# robotrev2.net
KiCad netlist of a schematic drawn in EAGLE
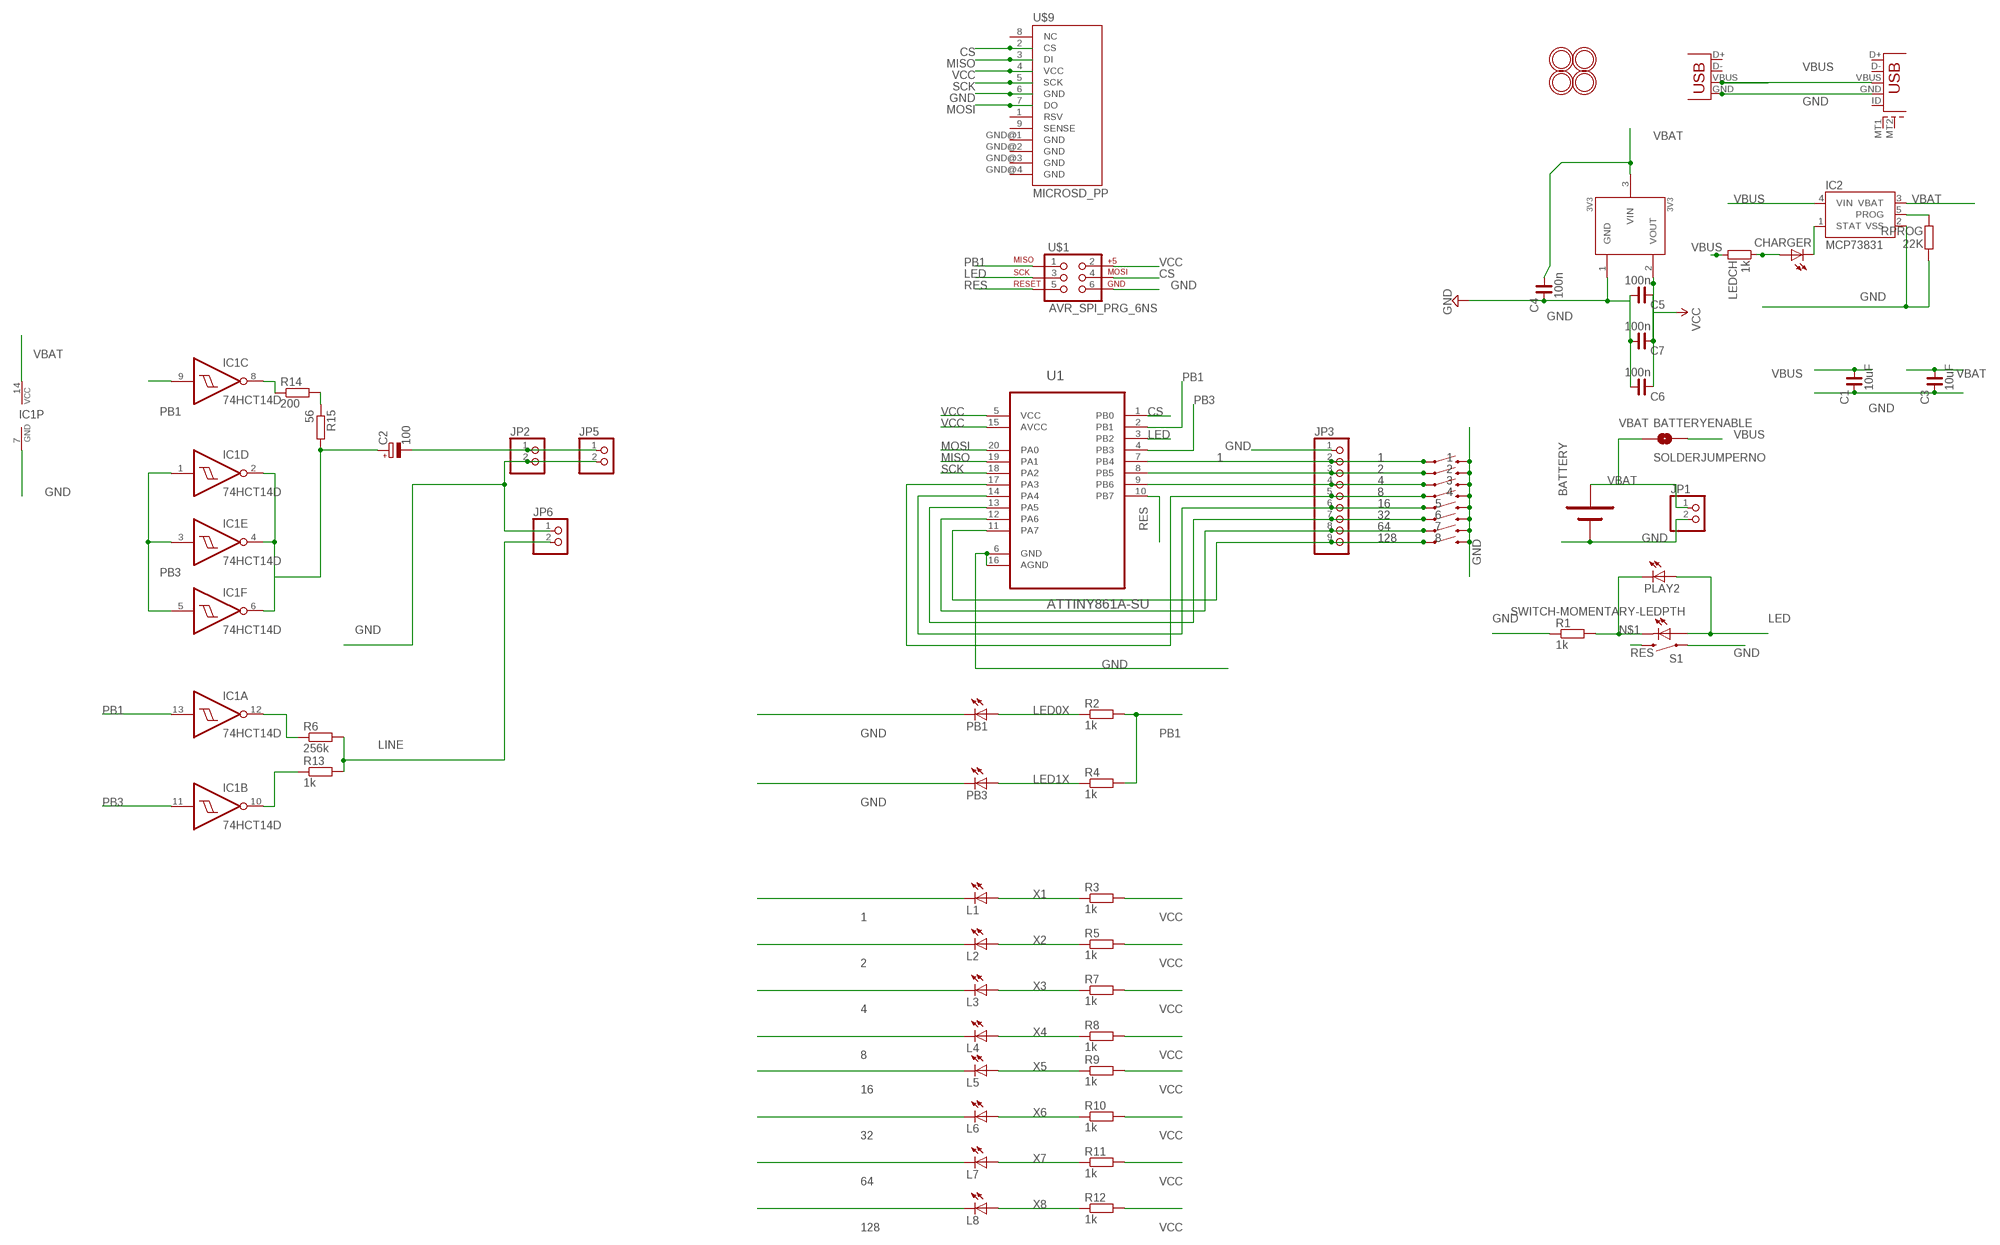
[diagram p0: schematic, sheet 1]

(export (version "E")
  (design (tool "Eeschema 10.0.6"))
  (components
    (comp (ref "1")
      (value "SWITCH-MOMENTARY-2-SMD-1101NE")
      (footprint "eagle-import:TACTILE-SWITCH-1101NE")
      (libsource (lib "eagle-import") (part "SWITCH-MOMENTARY-2-SMD-1101NE"))
    )
    (comp (ref "2")
      (value "SWITCH-MOMENTARY-2-SMD-1101NE")
      (footprint "eagle-import:TACTILE-SWITCH-1101NE")
      (libsource (lib "eagle-import") (part "SWITCH-MOMENTARY-2-SMD-1101NE"))
    )
    (comp (ref "3")
      (value "SWITCH-MOMENTARY-2-SMD-1101NE")
      (footprint "eagle-import:TACTILE-SWITCH-1101NE")
      (libsource (lib "eagle-import") (part "SWITCH-MOMENTARY-2-SMD-1101NE"))
    )
    (comp (ref "3V3")
      (value "3V3")
      (footprint "eagle-import:SOT23")
      (libsource (lib "eagle-import") (part "MCP1700T"))
    )
    (comp (ref "4")
      (value "SWITCH-MOMENTARY-2-SMD-1101NE")
      (footprint "eagle-import:TACTILE-SWITCH-1101NE")
      (libsource (lib "eagle-import") (part "SWITCH-MOMENTARY-2-SMD-1101NE"))
    )
    (comp (ref "5")
      (value "SWITCH-MOMENTARY-2-SMD-1101NE")
      (footprint "eagle-import:TACTILE-SWITCH-1101NE")
      (libsource (lib "eagle-import") (part "SWITCH-MOMENTARY-2-SMD-1101NE"))
    )
    (comp (ref "6")
      (value "SWITCH-MOMENTARY-2-SMD-1101NE")
      (footprint "eagle-import:TACTILE-SWITCH-1101NE")
      (libsource (lib "eagle-import") (part "SWITCH-MOMENTARY-2-SMD-1101NE"))
    )
    (comp (ref "7")
      (value "SWITCH-MOMENTARY-2-SMD-1101NE")
      (footprint "eagle-import:TACTILE-SWITCH-1101NE")
      (libsource (lib "eagle-import") (part "SWITCH-MOMENTARY-2-SMD-1101NE"))
    )
    (comp (ref "8")
      (value "SWITCH-MOMENTARY-2-SMD-1101NE")
      (footprint "eagle-import:TACTILE-SWITCH-1101NE")
      (libsource (lib "eagle-import") (part "SWITCH-MOMENTARY-2-SMD-1101NE"))
    )
    (comp (ref "BATTERY")
      (value "BATTERY-1XAA20MM")
      (footprint "eagle-import:BATTCOM_20MM_PTH")
      (libsource (lib "eagle-import") (part "BATTERY-1XAA20MM"))
    )
    (comp (ref "BATTERYENABLE")
      (value "SOLDERJUMPERNO")
      (footprint "eagle-import:SJ_2S-NO")
      (libsource (lib "eagle-import") (part "SOLDERJUMPERNO"))
    )
    (comp (ref "C1")
      (value "10uF")
      (footprint "eagle-import:C0603")
      (libsource (lib "eagle-import") (part "C_0603"))
    )
    (comp (ref "C2")
      (value "100")
      (footprint "eagle-import:153CLV-0605")
      (libsource (lib "eagle-import") (part "CPOL-EU153CLV-0605"))
    )
    (comp (ref "C3")
      (value "10uF")
      (footprint "eagle-import:C0603")
      (libsource (lib "eagle-import") (part "C_0603"))
    )
    (comp (ref "C4")
      (value "100n")
      (footprint "eagle-import:C0603")
      (libsource (lib "eagle-import") (part "C_0603"))
    )
    (comp (ref "C5")
      (value "100n")
      (footprint "eagle-import:C0603")
      (libsource (lib "eagle-import") (part "C_0603"))
    )
    (comp (ref "C6")
      (value "100n")
      (footprint "eagle-import:C0603")
      (libsource (lib "eagle-import") (part "C_0603"))
    )
    (comp (ref "C7")
      (value "100n")
      (footprint "eagle-import:C0603")
      (libsource (lib "eagle-import") (part "C_0603"))
    )
    (comp (ref "CHARGER")
      (value "LEDSML0603")
      (footprint "eagle-import:SML0603")
      (libsource (lib "eagle-import") (part "LEDSML0603"))
    )
    (comp (ref "IC1")
      (value "74HCT14D")
      (footprint "eagle-import:SO14")
      (libsource (lib "eagle-import") (part "7414DHCT"))
    )
    (comp (ref "IC2")
      (value "MCP73831")
      (footprint "eagle-import:SOT23-5")
      (libsource (lib "eagle-import") (part "MCP73831"))
    )
    (comp (ref "JP1")
      (value "PINHD-1X2")
      (footprint "eagle-import:1X02")
      (libsource (lib "eagle-import") (part "PINHD-1X2"))
    )
    (comp (ref "JP2")
      (value "PINHD-1X2")
      (footprint "eagle-import:1X02")
      (libsource (lib "eagle-import") (part "PINHD-1X2"))
    )
    (comp (ref "JP3")
      (value "PINHD-1X9")
      (footprint "eagle-import:1X09")
      (libsource (lib "eagle-import") (part "PINHD-1X9"))
    )
    (comp (ref "JP5")
      (value "PINHD-1X2")
      (footprint "eagle-import:1X02")
      (libsource (lib "eagle-import") (part "PINHD-1X2"))
    )
    (comp (ref "JP6")
      (value "PINHD-1X2")
      (footprint "eagle-import:1X02")
      (libsource (lib "eagle-import") (part "PINHD-1X2"))
    )
    (comp (ref "L1")
      (value "LEDSML0603")
      (footprint "eagle-import:SML0603")
      (libsource (lib "eagle-import") (part "LEDSML0603"))
    )
    (comp (ref "L2")
      (value "LEDSML0603")
      (footprint "eagle-import:SML0603")
      (libsource (lib "eagle-import") (part "LEDSML0603"))
    )
    (comp (ref "L3")
      (value "LEDSML0603")
      (footprint "eagle-import:SML0603")
      (libsource (lib "eagle-import") (part "LEDSML0603"))
    )
    (comp (ref "L4")
      (value "LEDSML0603")
      (footprint "eagle-import:SML0603")
      (libsource (lib "eagle-import") (part "LEDSML0603"))
    )
    (comp (ref "L5")
      (value "LEDSML0603")
      (footprint "eagle-import:SML0603")
      (libsource (lib "eagle-import") (part "LEDSML0603"))
    )
    (comp (ref "L6")
      (value "LEDSML0603")
      (footprint "eagle-import:SML0603")
      (libsource (lib "eagle-import") (part "LEDSML0603"))
    )
    (comp (ref "L7")
      (value "LEDSML0603")
      (footprint "eagle-import:SML0603")
      (libsource (lib "eagle-import") (part "LEDSML0603"))
    )
    (comp (ref "L8")
      (value "LEDSML0603")
      (footprint "eagle-import:SML0603")
      (libsource (lib "eagle-import") (part "LEDSML0603"))
    )
    (comp (ref "LEDCH")
      (value "1k")
      (footprint "eagle-import:R0603")
      (libsource (lib "eagle-import") (part "R-EU_R0603"))
    )
    (comp (ref "PB1")
      (value "LEDSML0603")
      (footprint "eagle-import:SML0603")
      (libsource (lib "eagle-import") (part "LEDSML0603"))
    )
    (comp (ref "PB3")
      (value "LEDSML0603")
      (footprint "eagle-import:SML0603")
      (libsource (lib "eagle-import") (part "LEDSML0603"))
    )
    (comp (ref "PLAY2")
      (value "LEDSML0603")
      (footprint "eagle-import:SML0603")
      (libsource (lib "eagle-import") (part "LEDSML0603"))
    )
    (comp (ref "R1")
      (value "1k")
      (footprint "eagle-import:R0603")
      (libsource (lib "eagle-import") (part "resistor_R-EU_R0603"))
    )
    (comp (ref "R2")
      (value "1k")
      (footprint "eagle-import:R0603")
      (libsource (lib "eagle-import") (part "resistor_R-EU_R0603"))
    )
    (comp (ref "R3")
      (value "1k")
      (footprint "eagle-import:R0603")
      (libsource (lib "eagle-import") (part "resistor_R-EU_R0603"))
    )
    (comp (ref "R4")
      (value "1k")
      (footprint "eagle-import:R0603")
      (libsource (lib "eagle-import") (part "resistor_R-EU_R0603"))
    )
    (comp (ref "R5")
      (value "1k")
      (footprint "eagle-import:R0603")
      (libsource (lib "eagle-import") (part "resistor_R-EU_R0603"))
    )
    (comp (ref "R6")
      (value "256k")
      (footprint "eagle-import:R0603")
      (libsource (lib "eagle-import") (part "resistor_R-EU_R0603"))
    )
    (comp (ref "R7")
      (value "1k")
      (footprint "eagle-import:R0603")
      (libsource (lib "eagle-import") (part "resistor_R-EU_R0603"))
    )
    (comp (ref "R8")
      (value "1k")
      (footprint "eagle-import:R0603")
      (libsource (lib "eagle-import") (part "resistor_R-EU_R0603"))
    )
    (comp (ref "R9")
      (value "1k")
      (footprint "eagle-import:R0603")
      (libsource (lib "eagle-import") (part "resistor_R-EU_R0603"))
    )
    (comp (ref "R10")
      (value "1k")
      (footprint "eagle-import:R0603")
      (libsource (lib "eagle-import") (part "resistor_R-EU_R0603"))
    )
    (comp (ref "R11")
      (value "1k")
      (footprint "eagle-import:R0603")
      (libsource (lib "eagle-import") (part "resistor_R-EU_R0603"))
    )
    (comp (ref "R12")
      (value "1k")
      (footprint "eagle-import:R0603")
      (libsource (lib "eagle-import") (part "resistor_R-EU_R0603"))
    )
    (comp (ref "R13")
      (value "1k")
      (footprint "eagle-import:R0603")
      (libsource (lib "eagle-import") (part "resistor_R-EU_R0603"))
    )
    (comp (ref "R14")
      (value "200")
      (footprint "eagle-import:R0603")
      (libsource (lib "eagle-import") (part "resistor_R-EU_R0603"))
    )
    (comp (ref "R15")
      (value "56")
      (footprint "eagle-import:R0603")
      (libsource (lib "eagle-import") (part "resistor_R-EU_R0603"))
    )
    (comp (ref "RPROG")
      (value "22K")
      (footprint "eagle-import:R0603")
      (libsource (lib "eagle-import") (part "R-EU_R0603"))
    )
    (comp (ref "S1")
      (value "SWITCH-MOMENTARY-LEDPTH")
      (footprint "eagle-import:TACTILE-PTH-LED-12MM")
      (libsource (lib "eagle-import") (part "SWITCH-MOMENTARY-LEDPTH"))
    )
    (comp (ref "U$1")
      (value "AVR_SPI_PRG_6NS")
      (footprint "eagle-import:2X3-NS")
      (libsource (lib "eagle-import") (part "AVR_SPI_PRG_6NS"))
    )
    (comp (ref "U$3")
      (value "MOUNTINGHOLE2.0")
      (footprint "eagle-import:MOUNTINGHOLE_2.0_PLATED")
      (libsource (lib "eagle-import") (part "MOUNTINGHOLE2.0"))
    )
    (comp (ref "U$4")
      (value "MOUNTINGHOLE2.0")
      (footprint "eagle-import:MOUNTINGHOLE_2.0_PLATED")
      (libsource (lib "eagle-import") (part "MOUNTINGHOLE2.0"))
    )
    (comp (ref "U$6")
      (value "MOUNTINGHOLE2.0")
      (footprint "eagle-import:MOUNTINGHOLE_2.0_PLATED")
      (libsource (lib "eagle-import") (part "MOUNTINGHOLE2.0"))
    )
    (comp (ref "U$7")
      (value "MOUNTINGHOLE2.0")
      (footprint "eagle-import:MOUNTINGHOLE_2.0_PLATED")
      (libsource (lib "eagle-import") (part "MOUNTINGHOLE2.0"))
    )
    (comp (ref "U$9")
      (value "MICROSD_PP")
      (footprint "eagle-import:MICROSD_PP")
      (libsource (lib "eagle-import") (part "MICROSD_PP"))
    )
    (comp (ref "U1")
      (value "ATTINY861A-SU")
      (footprint "eagle-import:SOIC127P1032X265-20N")
      (libsource (lib "eagle-import") (part "ATTINY861A-SU"))
    )
    (comp (ref "USB1")
      (value "USB-MICROBLARGEPAD")
      (footprint "eagle-import:USB-MICROB_LARGEPAD")
      (libsource (lib "eagle-import") (part "USB-MICROBLARGEPAD"))
    )
    (comp (ref "X5")
      (value "USBSMD")
      (footprint "eagle-import:USB-MINIB")
      (libsource (lib "eagle-import") (part "USBSMD"))
    )
  )
  (nets
    (net (code "1") (name "/1") (class "Default")
      (node (ref "1") (pin "P$1") (pinfunction "1_P$1") (pintype "passive"))
      (node (ref "JP3") (pin "2") (pinfunction "2_2") (pintype "passive"))
      (node (ref "L1") (pin "C") (pinfunction "C_C") (pintype "passive"))
      (node (ref "U1") (pin "7") (pinfunction "PB4_7") (pintype "bidirectional"))
    )
    (net (code "2") (name "/2") (class "Default")
      (node (ref "2") (pin "P$1") (pinfunction "1_P$1") (pintype "passive"))
      (node (ref "JP3") (pin "3") (pinfunction "3_3") (pintype "passive"))
      (node (ref "L2") (pin "C") (pinfunction "C_C") (pintype "passive"))
      (node (ref "U1") (pin "8") (pinfunction "PB5_8") (pintype "bidirectional"))
    )
    (net (code "3") (name "/4") (class "Default")
      (node (ref "3") (pin "P$1") (pinfunction "1_P$1") (pintype "passive"))
      (node (ref "JP3") (pin "4") (pinfunction "4_4") (pintype "passive"))
      (node (ref "L3") (pin "C") (pinfunction "C_C") (pintype "passive"))
      (node (ref "U1") (pin "9") (pinfunction "PB6_9") (pintype "bidirectional"))
    )
    (net (code "4") (name "/8") (class "Default")
      (node (ref "4") (pin "P$1") (pinfunction "1_P$1") (pintype "passive"))
      (node (ref "JP3") (pin "5") (pinfunction "5_5") (pintype "passive"))
      (node (ref "L4") (pin "C") (pinfunction "C_C") (pintype "passive"))
      (node (ref "U1") (pin "17") (pinfunction "PA3_17") (pintype "bidirectional"))
    )
    (net (code "5") (name "/16") (class "Default")
      (node (ref "5") (pin "P$1") (pinfunction "1_P$1") (pintype "passive"))
      (node (ref "JP3") (pin "6") (pinfunction "6_6") (pintype "passive"))
      (node (ref "L5") (pin "C") (pinfunction "C_C") (pintype "passive"))
      (node (ref "U1") (pin "14") (pinfunction "PA4_14") (pintype "bidirectional"))
    )
    (net (code "6") (name "/32") (class "Default")
      (node (ref "6") (pin "P$1") (pinfunction "1_P$1") (pintype "passive"))
      (node (ref "JP3") (pin "7") (pinfunction "7_7") (pintype "passive"))
      (node (ref "L6") (pin "C") (pinfunction "C_C") (pintype "passive"))
      (node (ref "U1") (pin "13") (pinfunction "PA5_13") (pintype "bidirectional"))
    )
    (net (code "7") (name "/64") (class "Default")
      (node (ref "7") (pin "P$1") (pinfunction "1_P$1") (pintype "passive"))
      (node (ref "JP3") (pin "8") (pinfunction "8_8") (pintype "passive"))
      (node (ref "L7") (pin "C") (pinfunction "C_C") (pintype "passive"))
      (node (ref "U1") (pin "12") (pinfunction "PA6_12") (pintype "bidirectional"))
    )
    (net (code "8") (name "/128") (class "Default")
      (node (ref "8") (pin "P$1") (pinfunction "1_P$1") (pintype "passive"))
      (node (ref "JP3") (pin "9") (pinfunction "9_9") (pintype "passive"))
      (node (ref "L8") (pin "C") (pinfunction "C_C") (pintype "passive"))
      (node (ref "U1") (pin "11") (pinfunction "PA7_11") (pintype "bidirectional"))
    )
    (net (code "9") (name "/CS") (class "Default")
      (node (ref "U$1") (pin "4") (pinfunction "4_4") (pintype "passive"))
      (node (ref "U$9") (pin "2") (pinfunction "CS_2") (pintype "bidirectional"))
      (node (ref "U1") (pin "1") (pinfunction "PB0_1") (pintype "bidirectional"))
    )
    (net (code "10") (name "/LED") (class "Default")
      (node (ref "PLAY2") (pin "A") (pinfunction "A_A") (pintype "passive"))
      (node (ref "S1") (pin "A") (pinfunction "A_A") (pintype "passive"))
      (node (ref "U$1") (pin "3") (pinfunction "3_3") (pintype "passive"))
      (node (ref "U1") (pin "3") (pinfunction "PB2_3") (pintype "bidirectional"))
    )
    (net (code "11") (name "/LED0X") (class "Default")
      (node (ref "PB1") (pin "A") (pinfunction "A_A") (pintype "passive"))
      (node (ref "R2") (pin "1") (pinfunction "1_1") (pintype "passive"))
    )
    (net (code "12") (name "/LED1X") (class "Default")
      (node (ref "PB3") (pin "A") (pinfunction "A_A") (pintype "passive"))
      (node (ref "R4") (pin "1") (pinfunction "1_1") (pintype "passive"))
    )
    (net (code "13") (name "/LINE") (class "Default")
      (node (ref "JP6") (pin "2") (pinfunction "2_2") (pintype "passive"))
      (node (ref "R13") (pin "2") (pinfunction "2_2") (pintype "passive"))
      (node (ref "R6") (pin "2") (pinfunction "2_2") (pintype "passive"))
    )
    (net (code "14") (name "/MISO") (class "Default")
      (node (ref "U$9") (pin "3") (pinfunction "DI_3") (pintype "bidirectional"))
      (node (ref "U1") (pin "19") (pinfunction "PA1_19") (pintype "bidirectional"))
    )
    (net (code "15") (name "/MOSI") (class "Default")
      (node (ref "U$9") (pin "7") (pinfunction "DO_7") (pintype "bidirectional"))
      (node (ref "U1") (pin "20") (pinfunction "PA0_20") (pintype "bidirectional"))
    )
    (net (code "16") (name "/N$1") (class "Default")
      (node (ref "PLAY2") (pin "C") (pinfunction "C_C") (pintype "passive"))
      (node (ref "R1") (pin "2") (pinfunction "2_2") (pintype "passive"))
      (node (ref "S1") (pin "C") (pinfunction "C_C") (pintype "passive"))
    )
    (net (code "17") (name "/PB1") (class "Default")
      (node (ref "IC1") (pin "13") (pinfunction "I_13") (pintype "input"))
      (node (ref "IC1") (pin "9") (pinfunction "I_9") (pintype "input"))
      (node (ref "R2") (pin "2") (pinfunction "2_2") (pintype "passive"))
      (node (ref "R4") (pin "2") (pinfunction "2_2") (pintype "passive"))
      (node (ref "U$1") (pin "1") (pinfunction "1_1") (pintype "passive"))
      (node (ref "U1") (pin "2") (pinfunction "PB1_2") (pintype "bidirectional"))
    )
    (net (code "18") (name "/PB3") (class "Default")
      (node (ref "IC1") (pin "1") (pinfunction "I_1") (pintype "input"))
      (node (ref "IC1") (pin "11") (pinfunction "I_11") (pintype "input"))
      (node (ref "IC1") (pin "3") (pinfunction "I_3") (pintype "input"))
      (node (ref "IC1") (pin "5") (pinfunction "I_5") (pintype "input"))
      (node (ref "U1") (pin "4") (pinfunction "PB3_4") (pintype "bidirectional"))
    )
    (net (code "19") (name "/RES") (class "Default")
      (node (ref "S1") (pin "2") (pinfunction "2_2") (pintype "passive"))
      (node (ref "U$1") (pin "5") (pinfunction "5_5") (pintype "passive"))
      (node (ref "U1") (pin "10") (pinfunction "PB7_10") (pintype "bidirectional"))
    )
    (net (code "20") (name "/SCK") (class "Default")
      (node (ref "U$9") (pin "5") (pinfunction "SCK_5") (pintype "bidirectional"))
      (node (ref "U1") (pin "18") (pinfunction "PA2_18") (pintype "bidirectional"))
    )
    (net (code "21") (name "/VBAT") (class "Default")
      (node (ref "3V3") (pin "3") (pinfunction "VIN_3") (pintype "bidirectional"))
      (node (ref "BATTERY") (pin "+") (pinfunction "+_+") (pintype "bidirectional"))
      (node (ref "BATTERYENABLE") (pin "1") (pinfunction "1_1") (pintype "passive"))
      (node (ref "C3") (pin "1") (pinfunction "1_1") (pintype "passive"))
      (node (ref "C4") (pin "1") (pinfunction "1_1") (pintype "passive"))
      (node (ref "IC1") (pin "14") (pinfunction "VCC_14") (pintype "power_in"))
      (node (ref "IC2") (pin "3") (pinfunction "VBAT_3") (pintype "power_in"))
      (node (ref "JP1") (pin "1") (pinfunction "1_1") (pintype "passive"))
    )
    (net (code "22") (name "/VBUS") (class "Default")
      (node (ref "BATTERYENABLE") (pin "2") (pinfunction "2_2") (pintype "passive"))
      (node (ref "C1") (pin "1") (pinfunction "1_1") (pintype "passive"))
      (node (ref "IC2") (pin "4") (pinfunction "VIN_4") (pintype "power_in"))
      (node (ref "LEDCH") (pin "2") (pinfunction "2_2") (pintype "passive"))
      (node (ref "USB1") (pin "VBUS") (pinfunction "VBUS_VBUS") (pintype "bidirectional"))
      (node (ref "X5") (pin "VBUS") (pinfunction "VBUS_VBUS") (pintype "bidirectional"))
    )
    (net (code "23") (name "/X1") (class "Default")
      (node (ref "L1") (pin "A") (pinfunction "A_A") (pintype "passive"))
      (node (ref "R3") (pin "1") (pinfunction "1_1") (pintype "passive"))
    )
    (net (code "24") (name "/X2") (class "Default")
      (node (ref "L2") (pin "A") (pinfunction "A_A") (pintype "passive"))
      (node (ref "R5") (pin "1") (pinfunction "1_1") (pintype "passive"))
    )
    (net (code "25") (name "/X3") (class "Default")
      (node (ref "L3") (pin "A") (pinfunction "A_A") (pintype "passive"))
      (node (ref "R7") (pin "1") (pinfunction "1_1") (pintype "passive"))
    )
    (net (code "26") (name "/X4") (class "Default")
      (node (ref "L4") (pin "A") (pinfunction "A_A") (pintype "passive"))
      (node (ref "R8") (pin "1") (pinfunction "1_1") (pintype "passive"))
    )
    (net (code "27") (name "/X5") (class "Default")
      (node (ref "L5") (pin "A") (pinfunction "A_A") (pintype "passive"))
      (node (ref "R9") (pin "1") (pinfunction "1_1") (pintype "passive"))
    )
    (net (code "28") (name "/X6") (class "Default")
      (node (ref "L6") (pin "A") (pinfunction "A_A") (pintype "passive"))
      (node (ref "R10") (pin "1") (pinfunction "1_1") (pintype "passive"))
    )
    (net (code "29") (name "/X7") (class "Default")
      (node (ref "L7") (pin "A") (pinfunction "A_A") (pintype "passive"))
      (node (ref "R11") (pin "1") (pinfunction "1_1") (pintype "passive"))
    )
    (net (code "30") (name "/X8") (class "Default")
      (node (ref "L8") (pin "A") (pinfunction "A_A") (pintype "passive"))
      (node (ref "R12") (pin "1") (pinfunction "1_1") (pintype "passive"))
    )
    (net (code "31") (name "GND") (class "Default")
      (node (ref "1") (pin "P$2") (pinfunction "2_P$2") (pintype "passive"))
      (node (ref "2") (pin "P$2") (pinfunction "2_P$2") (pintype "passive"))
      (node (ref "3") (pin "P$2") (pinfunction "2_P$2") (pintype "passive"))
      (node (ref "3V3") (pin "1") (pinfunction "GND_1") (pintype "bidirectional"))
      (node (ref "4") (pin "P$2") (pinfunction "2_P$2") (pintype "passive"))
      (node (ref "5") (pin "P$2") (pinfunction "2_P$2") (pintype "passive"))
      (node (ref "6") (pin "P$2") (pinfunction "2_P$2") (pintype "passive"))
      (node (ref "7") (pin "P$2") (pinfunction "2_P$2") (pintype "passive"))
      (node (ref "8") (pin "P$2") (pinfunction "2_P$2") (pintype "passive"))
      (node (ref "BATTERY") (pin "-") (pinfunction "-_-") (pintype "bidirectional"))
      (node (ref "C1") (pin "2") (pinfunction "2_2") (pintype "passive"))
      (node (ref "C3") (pin "2") (pinfunction "2_2") (pintype "passive"))
      (node (ref "C4") (pin "2") (pinfunction "2_2") (pintype "passive"))
      (node (ref "C5") (pin "1") (pinfunction "1_1") (pintype "passive"))
      (node (ref "C6") (pin "1") (pinfunction "1_1") (pintype "passive"))
      (node (ref "C7") (pin "1") (pinfunction "1_1") (pintype "passive"))
      (node (ref "IC1") (pin "7") (pinfunction "GND_7") (pintype "power_in"))
      (node (ref "IC2") (pin "2") (pinfunction "VSS_2") (pintype "power_in"))
      (node (ref "JP1") (pin "2") (pinfunction "2_2") (pintype "passive"))
      (node (ref "JP2") (pin "2") (pinfunction "2_2") (pintype "passive"))
      (node (ref "JP3") (pin "1") (pinfunction "1_1") (pintype "passive"))
      (node (ref "JP5") (pin "2") (pinfunction "2_2") (pintype "passive"))
      (node (ref "JP6") (pin "1") (pinfunction "1_1") (pintype "passive"))
      (node (ref "PB1") (pin "C") (pinfunction "C_C") (pintype "passive"))
      (node (ref "PB3") (pin "C") (pinfunction "C_C") (pintype "passive"))
      (node (ref "R1") (pin "1") (pinfunction "1_1") (pintype "passive"))
      (node (ref "RPROG") (pin "1") (pinfunction "1_1") (pintype "passive"))
      (node (ref "S1") (pin "4") (pinfunction "1_4") (pintype "passive"))
      (node (ref "U$1") (pin "6") (pinfunction "6_6") (pintype "passive"))
      (node (ref "U$9") (pin "6") (pinfunction "GND_6") (pintype "bidirectional"))
      (node (ref "U1") (pin "16") (pinfunction "AGND_16") (pintype "passive"))
      (node (ref "U1") (pin "6") (pinfunction "GND_6") (pintype "passive"))
      (node (ref "USB1") (pin "GND") (pinfunction "GND_GND") (pintype "bidirectional"))
      (node (ref "X5") (pin "GND") (pinfunction "GND_GND") (pintype "bidirectional"))
    )
    (net (code "32") (name "Net-(C2-Pad-)") (class "Default")
      (node (ref "C2") (pin "-") (pinfunction "-_-") (pintype "passive"))
      (node (ref "JP2") (pin "1") (pinfunction "1_1") (pintype "passive"))
      (node (ref "JP5") (pin "1") (pinfunction "1_1") (pintype "passive"))
    )
    (net (code "33") (name "Net-(CHARGER-PadA)") (class "Default")
      (node (ref "CHARGER") (pin "A") (pinfunction "A_A") (pintype "passive"))
      (node (ref "LEDCH") (pin "1") (pinfunction "1_1") (pintype "passive"))
    )
    (net (code "34") (name "Net-(IC1A-O)") (class "Default")
      (node (ref "IC1") (pin "12") (pinfunction "O_12") (pintype "output"))
      (node (ref "R6") (pin "1") (pinfunction "1_1") (pintype "passive"))
    )
    (net (code "35") (name "Net-(IC1B-O)") (class "Default")
      (node (ref "IC1") (pin "10") (pinfunction "O_10") (pintype "output"))
      (node (ref "R13") (pin "1") (pinfunction "1_1") (pintype "passive"))
    )
    (net (code "36") (name "Net-(IC1C-O)") (class "Default")
      (node (ref "IC1") (pin "8") (pinfunction "O_8") (pintype "output"))
      (node (ref "R14") (pin "1") (pinfunction "1_1") (pintype "passive"))
    )
    (net (code "37") (name "Net-(IC1D-O)") (class "Default")
      (node (ref "C2") (pin "+") (pinfunction "+_+") (pintype "passive"))
      (node (ref "IC1") (pin "2") (pinfunction "O_2") (pintype "output"))
      (node (ref "IC1") (pin "4") (pinfunction "O_4") (pintype "output"))
      (node (ref "IC1") (pin "6") (pinfunction "O_6") (pintype "output"))
      (node (ref "R15") (pin "2") (pinfunction "2_2") (pintype "passive"))
    )
    (net (code "38") (name "Net-(IC2-PROG)") (class "Default")
      (node (ref "IC2") (pin "5") (pinfunction "PROG_5") (pintype "input"))
      (node (ref "RPROG") (pin "2") (pinfunction "2_2") (pintype "passive"))
    )
    (net (code "39") (name "Net-(IC2-STAT)") (class "Default")
      (node (ref "CHARGER") (pin "C") (pinfunction "C_C") (pintype "passive"))
      (node (ref "IC2") (pin "1") (pinfunction "STAT_1") (pintype "output"))
    )
    (net (code "40") (name "Net-(R14-Pad2)") (class "Default")
      (node (ref "R14") (pin "2") (pinfunction "2_2") (pintype "passive"))
      (node (ref "R15") (pin "1") (pinfunction "1_1") (pintype "passive"))
    )
    (net (code "41") (name "VCC") (class "Default")
      (node (ref "3V3") (pin "2") (pinfunction "VOUT_2") (pintype "bidirectional"))
      (node (ref "C5") (pin "2") (pinfunction "2_2") (pintype "passive"))
      (node (ref "C6") (pin "2") (pinfunction "2_2") (pintype "passive"))
      (node (ref "C7") (pin "2") (pinfunction "2_2") (pintype "passive"))
      (node (ref "R10") (pin "2") (pinfunction "2_2") (pintype "passive"))
      (node (ref "R11") (pin "2") (pinfunction "2_2") (pintype "passive"))
      (node (ref "R12") (pin "2") (pinfunction "2_2") (pintype "passive"))
      (node (ref "R3") (pin "2") (pinfunction "2_2") (pintype "passive"))
      (node (ref "R5") (pin "2") (pinfunction "2_2") (pintype "passive"))
      (node (ref "R7") (pin "2") (pinfunction "2_2") (pintype "passive"))
      (node (ref "R8") (pin "2") (pinfunction "2_2") (pintype "passive"))
      (node (ref "R9") (pin "2") (pinfunction "2_2") (pintype "passive"))
      (node (ref "U$1") (pin "2") (pinfunction "2_2") (pintype "passive"))
      (node (ref "U$9") (pin "4") (pinfunction "VCC_4") (pintype "bidirectional"))
      (node (ref "U1") (pin "15") (pinfunction "AVCC_15") (pintype "power_in"))
      (node (ref "U1") (pin "5") (pinfunction "VCC_5") (pintype "power_in"))
    )
    (net (code "42") (name "unconnected-(U$9-GND-PadGND@1)") (class "Default")
      (node (ref "U$9") (pin "GND@1") (pinfunction "GND_GND@1") (pintype "bidirectional"))
    )
    (net (code "43") (name "unconnected-(U$9-GND-PadGND@2)") (class "Default")
      (node (ref "U$9") (pin "GND@2") (pinfunction "GND_GND@2") (pintype "bidirectional"))
    )
    (net (code "44") (name "unconnected-(U$9-GND-PadGND@3)") (class "Default")
      (node (ref "U$9") (pin "GND@3") (pinfunction "GND_GND@3") (pintype "bidirectional"))
    )
    (net (code "45") (name "unconnected-(U$9-GND-PadGND@4)") (class "Default")
      (node (ref "U$9") (pin "GND@4") (pinfunction "GND_GND@4") (pintype "bidirectional"))
    )
    (net (code "46") (name "unconnected-(U$9-NC-Pad8)") (class "Default")
      (node (ref "U$9") (pin "8") (pinfunction "NC_8") (pintype "bidirectional"))
    )
    (net (code "47") (name "unconnected-(U$9-RSV-Pad1)") (class "Default")
      (node (ref "U$9") (pin "1") (pinfunction "RSV_1") (pintype "bidirectional"))
    )
    (net (code "48") (name "unconnected-(U$9-SENSE-Pad9)") (class "Default")
      (node (ref "U$9") (pin "9") (pinfunction "SENSE_9") (pintype "bidirectional"))
    )
    (net (code "49") (name "unconnected-(USB1-PadD+)") (class "Default")
      (node (ref "USB1") (pin "D+") (pinfunction "D+_D+") (pintype "bidirectional"))
    )
    (net (code "50") (name "unconnected-(USB1-PadD-)") (class "Default")
      (node (ref "USB1") (pin "D-") (pinfunction "D-_D-") (pintype "bidirectional"))
    )
    (net (code "51") (name "unconnected-(USB1-PadID)") (class "Default")
      (node (ref "USB1") (pin "ID") (pinfunction "ID_ID") (pintype "bidirectional"))
    )
    (net (code "52") (name "unconnected-(USB1-SHEILD1-PadMT1)") (class "Default")
      (node (ref "USB1") (pin "MT1") (pinfunction "SHEILD1_MT1") (pintype "bidirectional"))
    )
    (net (code "53") (name "unconnected-(USB1-SHEILD2-PadMT2)") (class "Default")
      (node (ref "USB1") (pin "MT2") (pinfunction "SHEILD2_MT2") (pintype "bidirectional"))
    )
    (net (code "54") (name "unconnected-(X5-PadD+)") (class "Default")
      (node (ref "X5") (pin "D+") (pinfunction "D+_D+") (pintype "bidirectional"))
    )
    (net (code "55") (name "unconnected-(X5-PadD-)") (class "Default")
      (node (ref "X5") (pin "D-") (pinfunction "D-_D-") (pintype "bidirectional"))
    )
  )
)
